# LED_Light.net
KiCad netlist of a schematic drawn in EAGLE
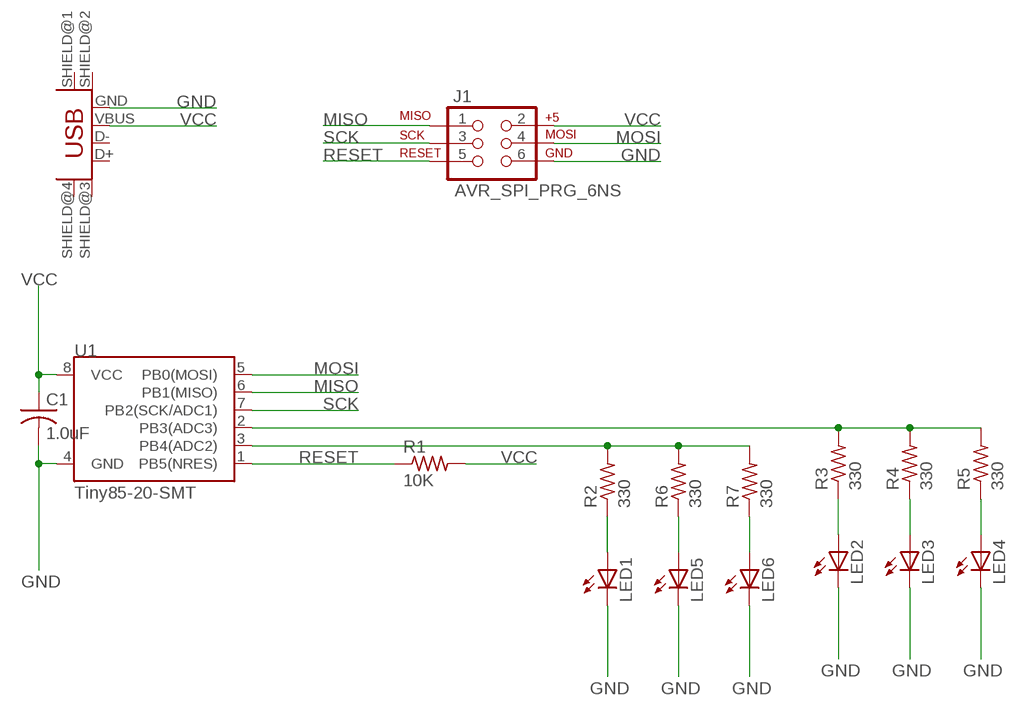
[diagram p0: schematic, sheet 1]

(export (version "E")
  (design (tool "Eeschema 10.0.6"))
  (components
    (comp (ref "C1")
      (value "1.0uF")
      (footprint "eagle-import:C1206")
      (libsource (lib "eagle-import") (part "C-USC1206"))
    )
    (comp (ref "J1")
      (value "AVR_SPI_PRG_6NS")
      (footprint "eagle-import:2X3-NS")
      (libsource (lib "eagle-import") (part "AVR_SPI_PRG_6NS"))
    )
    (comp (ref "JP1")
      (value "USB_MINIB")
      (footprint "eagle-import:USB_MINIB")
      (libsource (lib "eagle-import") (part "USB_MINIB"))
    )
    (comp (ref "LED1")
      (value "LEDSMT1206")
      (footprint "eagle-import:1206")
      (libsource (lib "eagle-import") (part "LEDSMT1206"))
    )
    (comp (ref "LED2")
      (value "LEDSMT1206")
      (footprint "eagle-import:1206")
      (libsource (lib "eagle-import") (part "LEDSMT1206"))
    )
    (comp (ref "LED3")
      (value "LEDSMT1206")
      (footprint "eagle-import:1206")
      (libsource (lib "eagle-import") (part "LEDSMT1206"))
    )
    (comp (ref "LED4")
      (value "LEDSMT1206")
      (footprint "eagle-import:1206")
      (libsource (lib "eagle-import") (part "LEDSMT1206"))
    )
    (comp (ref "LED5")
      (value "LEDSMT1206")
      (footprint "eagle-import:1206")
      (libsource (lib "eagle-import") (part "LEDSMT1206"))
    )
    (comp (ref "LED6")
      (value "LEDSMT1206")
      (footprint "eagle-import:1206")
      (libsource (lib "eagle-import") (part "LEDSMT1206"))
    )
    (comp (ref "R1")
      (value "10K")
      (footprint "eagle-import:R1206")
      (libsource (lib "eagle-import") (part "R-US_R1206"))
    )
    (comp (ref "R2")
      (value "330")
      (footprint "eagle-import:R1206")
      (libsource (lib "eagle-import") (part "R-US_R1206"))
    )
    (comp (ref "R3")
      (value "330")
      (footprint "eagle-import:R1206")
      (libsource (lib "eagle-import") (part "R-US_R1206"))
    )
    (comp (ref "R4")
      (value "330")
      (footprint "eagle-import:R1206")
      (libsource (lib "eagle-import") (part "R-US_R1206"))
    )
    (comp (ref "R5")
      (value "330")
      (footprint "eagle-import:R1206")
      (libsource (lib "eagle-import") (part "R-US_R1206"))
    )
    (comp (ref "R6")
      (value "330")
      (footprint "eagle-import:R1206")
      (libsource (lib "eagle-import") (part "R-US_R1206"))
    )
    (comp (ref "R7")
      (value "330")
      (footprint "eagle-import:R1206")
      (libsource (lib "eagle-import") (part "R-US_R1206"))
    )
    (comp (ref "U1")
      (value "Tiny85-20-SMT")
      (footprint "eagle-import:SO08-EIAJ")
      (libsource (lib "eagle-import") (part "ATTINY45TINY85-20-SMT"))
    )
  )
  (nets
    (net (code "1") (name "/GND") (class "Default")
      (node (ref "C1") (pin "2") (pinfunction "2_2") (pintype "passive"))
      (node (ref "J1") (pin "6") (pinfunction "6_6") (pintype "passive"))
      (node (ref "JP1") (pin "GND") (pinfunction "GND_GND") (pintype "bidirectional"))
      (node (ref "LED1") (pin "C") (pinfunction "C_C") (pintype "passive"))
      (node (ref "LED2") (pin "C") (pinfunction "C_C") (pintype "passive"))
      (node (ref "LED3") (pin "C") (pinfunction "C_C") (pintype "passive"))
      (node (ref "LED4") (pin "C") (pinfunction "C_C") (pintype "passive"))
      (node (ref "LED5") (pin "C") (pinfunction "C_C") (pintype "passive"))
      (node (ref "LED6") (pin "C") (pinfunction "C_C") (pintype "passive"))
      (node (ref "U1") (pin "4") (pinfunction "GND_4") (pintype "bidirectional"))
    )
    (net (code "2") (name "/MISO") (class "Default")
      (node (ref "J1") (pin "1") (pinfunction "1_1") (pintype "passive"))
      (node (ref "U1") (pin "6") (pinfunction "PB1(MISO)_6") (pintype "bidirectional"))
    )
    (net (code "3") (name "/MOSI") (class "Default")
      (node (ref "J1") (pin "4") (pinfunction "4_4") (pintype "passive"))
      (node (ref "U1") (pin "5") (pinfunction "PB0(MOSI)_5") (pintype "bidirectional"))
    )
    (net (code "4") (name "/RESET") (class "Default")
      (node (ref "J1") (pin "5") (pinfunction "5_5") (pintype "passive"))
      (node (ref "R1") (pin "1") (pinfunction "1_1") (pintype "passive"))
      (node (ref "U1") (pin "1") (pinfunction "PB5(NRES)_1") (pintype "bidirectional"))
    )
    (net (code "5") (name "/SCK") (class "Default")
      (node (ref "J1") (pin "3") (pinfunction "3_3") (pintype "passive"))
      (node (ref "U1") (pin "7") (pinfunction "PB2(SCK/ADC1)_7") (pintype "bidirectional"))
    )
    (net (code "6") (name "/VCC") (class "Default")
      (node (ref "C1") (pin "1") (pinfunction "1_1") (pintype "passive"))
      (node (ref "J1") (pin "2") (pinfunction "2_2") (pintype "passive"))
      (node (ref "JP1") (pin "VBUS") (pinfunction "VBUS_VBUS") (pintype "bidirectional"))
      (node (ref "R1") (pin "2") (pinfunction "2_2") (pintype "passive"))
      (node (ref "U1") (pin "8") (pinfunction "VCC_8") (pintype "bidirectional"))
    )
    (net (code "7") (name "Net-(LED1-PadA)") (class "Default")
      (node (ref "LED1") (pin "A") (pinfunction "A_A") (pintype "passive"))
      (node (ref "R2") (pin "1") (pinfunction "1_1") (pintype "passive"))
    )
    (net (code "8") (name "Net-(LED2-PadA)") (class "Default")
      (node (ref "LED2") (pin "A") (pinfunction "A_A") (pintype "passive"))
      (node (ref "R3") (pin "1") (pinfunction "1_1") (pintype "passive"))
    )
    (net (code "9") (name "Net-(LED3-PadA)") (class "Default")
      (node (ref "LED3") (pin "A") (pinfunction "A_A") (pintype "passive"))
      (node (ref "R4") (pin "1") (pinfunction "1_1") (pintype "passive"))
    )
    (net (code "10") (name "Net-(LED4-PadA)") (class "Default")
      (node (ref "LED4") (pin "A") (pinfunction "A_A") (pintype "passive"))
      (node (ref "R5") (pin "1") (pinfunction "1_1") (pintype "passive"))
    )
    (net (code "11") (name "Net-(LED5-PadA)") (class "Default")
      (node (ref "LED5") (pin "A") (pinfunction "A_A") (pintype "passive"))
      (node (ref "R6") (pin "1") (pinfunction "1_1") (pintype "passive"))
    )
    (net (code "12") (name "Net-(LED6-PadA)") (class "Default")
      (node (ref "LED6") (pin "A") (pinfunction "A_A") (pintype "passive"))
      (node (ref "R7") (pin "1") (pinfunction "1_1") (pintype "passive"))
    )
    (net (code "13") (name "Net-(U1-PB3(ADC3))") (class "Default")
      (node (ref "R3") (pin "2") (pinfunction "2_2") (pintype "passive"))
      (node (ref "R4") (pin "2") (pinfunction "2_2") (pintype "passive"))
      (node (ref "R5") (pin "2") (pinfunction "2_2") (pintype "passive"))
      (node (ref "U1") (pin "2") (pinfunction "PB3(ADC3)_2") (pintype "bidirectional"))
    )
    (net (code "14") (name "Net-(U1-PB4(ADC2))") (class "Default")
      (node (ref "R2") (pin "2") (pinfunction "2_2") (pintype "passive"))
      (node (ref "R6") (pin "2") (pinfunction "2_2") (pintype "passive"))
      (node (ref "R7") (pin "2") (pinfunction "2_2") (pintype "passive"))
      (node (ref "U1") (pin "3") (pinfunction "PB4(ADC2)_3") (pintype "bidirectional"))
    )
    (net (code "15") (name "unconnected-(JP1-PadD+)") (class "Default")
      (node (ref "JP1") (pin "D+") (pinfunction "D+_D+") (pintype "bidirectional"))
    )
    (net (code "16") (name "unconnected-(JP1-PadD-)") (class "Default")
      (node (ref "JP1") (pin "D-") (pinfunction "D-_D-") (pintype "bidirectional"))
    )
    (net (code "17") (name "unconnected-(JP1-SHIELD-PadSHIELD@1)") (class "Default")
      (node (ref "JP1") (pin "SHIELD@1") (pinfunction "SHIELD_SHIELD@1") (pintype "passive"))
    )
    (net (code "18") (name "unconnected-(JP1-SHIELD1-PadSHIELD@2)") (class "Default")
      (node (ref "JP1") (pin "SHIELD@2") (pinfunction "SHIELD1_SHIELD@2") (pintype "passive"))
    )
    (net (code "19") (name "unconnected-(JP1-SHIELD2-PadSHIELD@3)") (class "Default")
      (node (ref "JP1") (pin "SHIELD@3") (pinfunction "SHIELD2_SHIELD@3") (pintype "passive"))
    )
    (net (code "20") (name "unconnected-(JP1-SHIELD3-PadSHIELD@4)") (class "Default")
      (node (ref "JP1") (pin "SHIELD@4") (pinfunction "SHIELD3_SHIELD@4") (pintype "passive"))
    )
  )
)
